# Power.net
KiCad netlist of a schematic drawn in Altium Designer
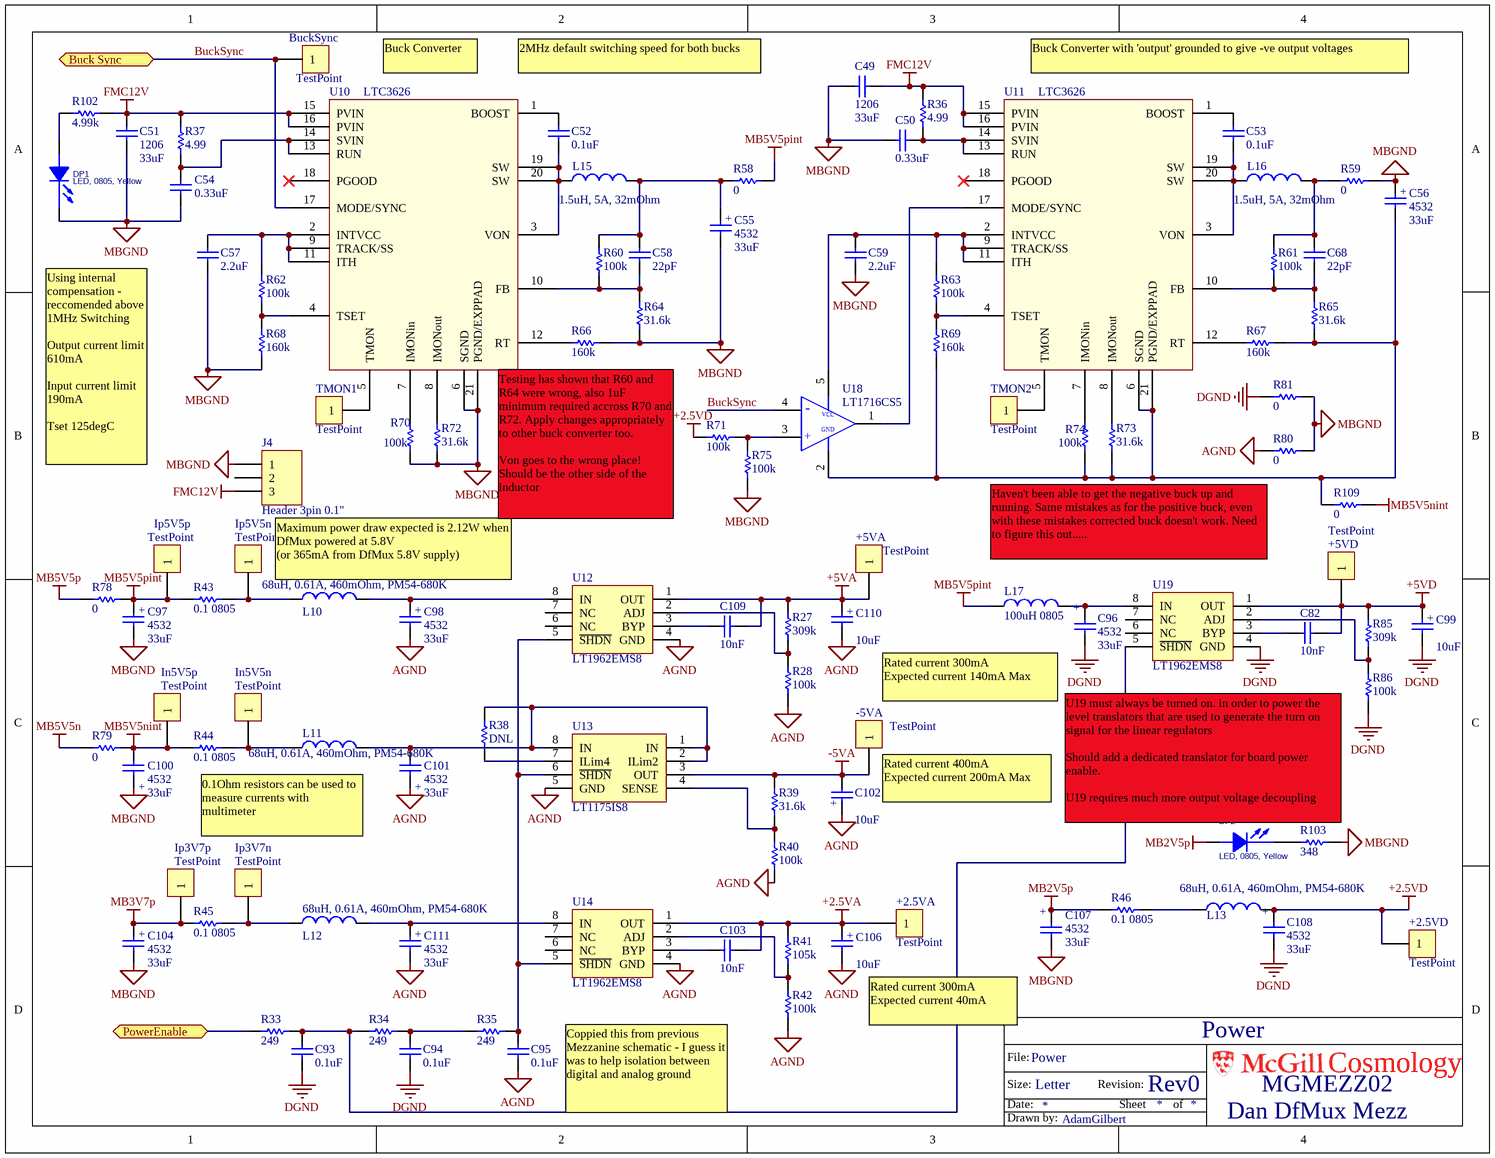
[diagram p0: Power.SchDoc]

(export (version "E")
  (design (tool "Eeschema 10.0.6"))
  (components
    (comp (ref "+2.5VA")
      (value "TestPoint")
      (footprint "TP-3520-SK")
      (description "TestPoint1")
      (libsource (lib "") (part "TestPoint_2"))
    )
    (comp (ref "+2.5VD")
      (value "TestPoint")
      (footprint "TP-3520-SK")
      (description "TestPoint1")
      (libsource (lib "") (part "TestPoint_2"))
    )
    (comp (ref "+5VA")
      (value "TestPoint")
      (footprint "TP-3520-SK")
      (description "TestPoint1")
      (libsource (lib "MGMEZZ04") (part "TestPoint"))
    )
    (comp (ref "+5VD")
      (value "TestPoint")
      (footprint "TP-3520-SK")
      (description "TestPoint1")
      (libsource (lib "MGMEZZ04") (part "TestPoint"))
    )
    (comp (ref "-5VA")
      (value "TestPoint")
      (footprint "TP-3520-SK")
      (description "TestPoint1")
      (libsource (lib "MGMEZZ04") (part "TestPoint"))
    )
    (comp (ref "BuckSync")
      (value "TestPoint")
      (footprint "TP-3520-SK")
      (description "TestPoint1")
      (libsource (lib "") (part "TestPoint_2"))
    )
    (comp (ref "C49")
      (value "33uF")
      (footprint "1206")
      (description "Capacitor, Ceramic, 1210")
      (fields
        (field (name "MANUFACTURER") "TDK Corporation")
        (field (name "MANUFACTURERS PART NUMBER") "C3216X5R1E336M")
      )
      (libsource (lib "MGMEZZ04") (part "CAP 1210"))
    )
    (comp (ref "C50")
      (value "0.33uF")
      (footprint "0603")
      (description "Capacitor, Ceramic, 0603")
      (fields (field (name "MANUFACTURER") "Generic"))
      (libsource (lib "MGMEZZ04") (part "CAP 0603"))
    )
    (comp (ref "C51")
      (value "33uF")
      (footprint "1206")
      (description "Capacitor, Ceramic, 1210")
      (fields
        (field (name "MANUFACTURER") "TDK Corporation")
        (field (name "MANUFACTURERS PART NUMBER") "C3216X5R1E336M")
      )
      (libsource (lib "MGMEZZ04") (part "CAP 1210"))
    )
    (comp (ref "C52")
      (value "0.1uF")
      (footprint "0603")
      (description "Capacitor, Ceramic, 0603")
      (fields (field (name "MANUFACTURER") "Generic"))
      (libsource (lib "MGMEZZ04") (part "CAP 0603"))
    )
    (comp (ref "C53")
      (value "0.1uF")
      (footprint "0603")
      (description "Capacitor, Ceramic, 0603")
      (fields (field (name "MANUFACTURER") "Generic"))
      (libsource (lib "MGMEZZ04") (part "CAP 0603"))
    )
    (comp (ref "C54")
      (value "0.33uF")
      (footprint "0603")
      (description "Capacitor, Ceramic, 0603")
      (fields (field (name "MANUFACTURER") "Generic"))
      (libsource (lib "MGMEZZ04") (part "CAP 0603"))
    )
    (comp (ref "C55")
      (value "33uF")
      (footprint "4532")
      (description "33u, 16V, 20%, 4532C, X5R")
      (fields
        (field (name "MANUFACTURER") "TDK Corporation")
        (field (name "MANUFACTURERS PART NUMBER") "C4532X5R1C336M")
      )
      (libsource (lib "MGMEZZ04") (part "CAP4532"))
    )
    (comp (ref "C56")
      (value "33uF")
      (footprint "4532")
      (description "33u, 16V, 20%, 4532C, X5R")
      (fields
        (field (name "MANUFACTURER") "TDK Corporation")
        (field (name "MANUFACTURERS PART NUMBER") "C4532X5R1C336M")
      )
      (libsource (lib "MGMEZZ04") (part "CAP4532"))
    )
    (comp (ref "C57")
      (value "2.2uF")
      (footprint "0603")
      (description "Capacitor, Ceramic, 0603")
      (fields (field (name "MANUFACTURER") "Generic"))
      (libsource (lib "MGMEZZ04") (part "CAP 0603"))
    )
    (comp (ref "C58")
      (value "22pF")
      (footprint "0603")
      (description "Capacitor, Ceramic, 0603")
      (fields (field (name "MANUFACTURER") "Generic"))
      (libsource (lib "MGMEZZ04") (part "CAP 0603"))
    )
    (comp (ref "C59")
      (value "2.2uF")
      (footprint "0603")
      (description "Capacitor, Ceramic, 0603")
      (fields (field (name "MANUFACTURER") "Generic"))
      (libsource (lib "MGMEZZ04") (part "CAP 0603"))
    )
    (comp (ref "C68")
      (value "22pF")
      (footprint "0603")
      (description "Capacitor, Ceramic, 0603")
      (fields (field (name "MANUFACTURER") "Generic"))
      (libsource (lib "MGMEZZ04") (part "CAP 0603"))
    )
    (comp (ref "C82")
      (value "10nF")
      (footprint "0603")
      (description "Capacitor, Ceramic, 0603")
      (fields (field (name "MANUFACTURER") "Generic"))
      (libsource (lib "MGMEZZ04") (part "CAP 0603"))
    )
    (comp (ref "C93")
      (value "0.1uF")
      (footprint "0603")
      (description "Capacitor, Ceramic, 0603")
      (fields (field (name "MANUFACTURER") "Generic"))
      (libsource (lib "MGMEZZ04") (part "CAP 0603"))
    )
    (comp (ref "C94")
      (value "0.1uF")
      (footprint "0603")
      (description "Capacitor, Ceramic, 0603")
      (fields (field (name "MANUFACTURER") "Generic"))
      (libsource (lib "MGMEZZ04") (part "CAP 0603"))
    )
    (comp (ref "C95")
      (value "0.1uF")
      (footprint "0603")
      (description "Capacitor, Ceramic, 0603")
      (fields (field (name "MANUFACTURER") "Generic"))
      (libsource (lib "MGMEZZ04") (part "CAP 0603"))
    )
    (comp (ref "C96")
      (value "33uF")
      (footprint "4532")
      (description "33u, 16V, 20%, 4532C, X5R")
      (fields
        (field (name "MANUFACTURER") "TDK Corporation")
        (field (name "MANUFACTURERS PART NUMBER") "C4532X5R1C336M")
      )
      (libsource (lib "MGMEZZ04") (part "CAP4532"))
    )
    (comp (ref "C97")
      (value "33uF")
      (footprint "4532")
      (description "33u, 16V, 20%, 4532C, X5R")
      (fields
        (field (name "MANUFACTURER") "TDK Corporation")
        (field (name "MANUFACTURERS PART NUMBER") "C4532X5R1C336M")
      )
      (libsource (lib "MGMEZZ04") (part "CAP4532"))
    )
    (comp (ref "C98")
      (value "33uF")
      (footprint "4532")
      (description "33u, 16V, 20%, 4532C, X5R")
      (fields
        (field (name "MANUFACTURER") "TDK Corporation")
        (field (name "MANUFACTURERS PART NUMBER") "C4532X5R1C336M")
      )
      (libsource (lib "MGMEZZ04") (part "CAP4532"))
    )
    (comp (ref "C99")
      (value "10uF")
      (footprint "TCASE-A")
      (description "TantA Cap")
      (fields (field (name "MANUFACTURER") "Generic"))
      (libsource (lib "MGMEZZ04") (part "CAP TANT CASE-A"))
    )
    (comp (ref "C100")
      (value "33uF")
      (footprint "4532")
      (description "33u, 16V, 20%, 4532C, X5R")
      (fields
        (field (name "MANUFACTURER") "TDK Corporation")
        (field (name "MANUFACTURERS PART NUMBER") "C4532X5R1C336M")
      )
      (libsource (lib "MGMEZZ04") (part "CAP4532"))
    )
    (comp (ref "C101")
      (value "33uF")
      (footprint "4532")
      (description "33u, 16V, 20%, 4532C, X5R")
      (fields
        (field (name "MANUFACTURER") "TDK Corporation")
        (field (name "MANUFACTURERS PART NUMBER") "C4532X5R1C336M")
      )
      (libsource (lib "MGMEZZ04") (part "CAP4532"))
    )
    (comp (ref "C102")
      (value "10uF")
      (footprint "TCASE-A")
      (description "TantA Cap")
      (fields (field (name "MANUFACTURER") "Generic"))
      (libsource (lib "MGMEZZ04") (part "CAP TANT CASE-A"))
    )
    (comp (ref "C103")
      (value "10nF")
      (footprint "0603")
      (description "Capacitor, Ceramic, 0603")
      (fields (field (name "MANUFACTURER") "Generic"))
      (libsource (lib "MGMEZZ04") (part "CAP 0603"))
    )
    (comp (ref "C104")
      (value "33uF")
      (footprint "4532")
      (description "33u, 16V, 20%, 4532C, X5R")
      (fields
        (field (name "MANUFACTURER") "TDK Corporation")
        (field (name "MANUFACTURERS PART NUMBER") "C4532X5R1C336M")
      )
      (libsource (lib "MGMEZZ04") (part "CAP4532"))
    )
    (comp (ref "C106")
      (value "10uF")
      (footprint "TCASE-A")
      (description "TantA Cap")
      (fields (field (name "MANUFACTURER") "Generic"))
      (libsource (lib "MGMEZZ04") (part "CAP TANT CASE-A"))
    )
    (comp (ref "C107")
      (value "33uF")
      (footprint "4532")
      (description "33u, 16V, 20%, 4532C, X5R")
      (fields
        (field (name "MANUFACTURER") "TDK Corporation")
        (field (name "MANUFACTURERS PART NUMBER") "C4532X5R1C336M")
      )
      (libsource (lib "MGMEZZ04") (part "CAP4532"))
    )
    (comp (ref "C108")
      (value "33uF")
      (footprint "4532")
      (description "33u, 16V, 20%, 4532C, X5R")
      (fields
        (field (name "MANUFACTURER") "TDK Corporation")
        (field (name "MANUFACTURERS PART NUMBER") "C4532X5R1C336M")
      )
      (libsource (lib "MGMEZZ04") (part "CAP4532"))
    )
    (comp (ref "C109")
      (value "10nF")
      (footprint "0603")
      (description "Capacitor, Ceramic, 0603")
      (fields (field (name "MANUFACTURER") "Generic"))
      (libsource (lib "MGMEZZ04") (part "CAP 0603"))
    )
    (comp (ref "C110")
      (value "10uF")
      (footprint "TCASE-A")
      (description "TantA Cap")
      (fields (field (name "MANUFACTURER") "Generic"))
      (libsource (lib "MGMEZZ04") (part "CAP TANT CASE-A"))
    )
    (comp (ref "C111")
      (value "33uF")
      (footprint "4532")
      (description "33u, 16V, 20%, 4532C, X5R")
      (fields
        (field (name "MANUFACTURER") "TDK Corporation")
        (field (name "MANUFACTURERS PART NUMBER") "C4532X5R1C336M")
      )
      (libsource (lib "MGMEZZ04") (part "CAP4532"))
    )
    (comp (ref "DP1")
      (value "LED, 0805, Yellow")
      (description "LED")
      (fields
        (field (name "MANUFACTURER") "Rohm Semiconductor")
        (field (name "MANUFACTURERS PART NUMBER") "SML-211YTT86")
      )
      (libsource (lib "MGMEZZ04") (part "LED, yellow, 0805, 2mA"))
    )
    (comp (ref "DP2")
      (value "LED, 0805, Yellow")
      (description "LED")
      (fields
        (field (name "MANUFACTURER") "Rohm Semiconductor")
        (field (name "MANUFACTURERS PART NUMBER") "SML-211YTT86")
      )
      (libsource (lib "MGMEZZ04") (part "LED, yellow, 0805, 2mA"))
    )
    (comp (ref "In5V5n")
      (value "TestPoint")
      (footprint "TP-3520-SK")
      (description "TestPoint1")
      (libsource (lib "MGMEZZ04") (part "TestPoint"))
    )
    (comp (ref "In5V5p")
      (value "TestPoint")
      (footprint "TP-3520-SK")
      (description "TestPoint1")
      (libsource (lib "MGMEZZ04") (part "TestPoint"))
    )
    (comp (ref "Ip3V7n")
      (value "TestPoint")
      (footprint "TP-3520-SK")
      (description "TestPoint1")
      (libsource (lib "MGMEZZ04") (part "TestPoint"))
    )
    (comp (ref "Ip3V7p")
      (value "TestPoint")
      (footprint "TP-3520-SK")
      (description "TestPoint1")
      (libsource (lib "MGMEZZ04") (part "TestPoint"))
    )
    (comp (ref "Ip5V5n")
      (value "TestPoint")
      (footprint "TP-3520-SK")
      (description "TestPoint1")
      (libsource (lib "MGMEZZ04") (part "TestPoint"))
    )
    (comp (ref "Ip5V5p")
      (value "TestPoint")
      (footprint "TP-3520-SK")
      (description "TestPoint1")
      (libsource (lib "MGMEZZ04") (part "TestPoint"))
    )
    (comp (ref "J4")
      (value "Header 3pin 0.1\"")
      (footprint "HDR1X3_MolexVertical")
      (description "Header, 0.1\"  3-Pin")
      (fields (field (name "MANUFACTURER") "Molex") (field (name "MANUFACTURERS PART NUMBER") "0099990987"))
      (libsource (lib "MGMEZZ04") (part "Header 3"))
    )
    (comp (ref "L10")
      (value "68uH")
      (footprint "CHOKEPM54")
      (description "Inductor PM54")
      (fields
        (field (name "MANUFACTURER") "Bourns Inc.")
        (field (name "MANUFACTURERS PART NUMBER") "PM54-680K")
        (field (name "PART CONSTRAINTS") "68uH, 0.61A, 460mOhm, PM54-680K")
      )
      (libsource (lib "") (part "INDPM54_1"))
    )
    (comp (ref "L11")
      (value "68uH")
      (footprint "CHOKEPM54")
      (description "Inductor PM54")
      (fields
        (field (name "MANUFACTURER") "Bourns Inc.")
        (field (name "MANUFACTURERS PART NUMBER") "PM54-680K")
        (field (name "PART CONSTRAINTS") "68uH, 0.61A, 460mOhm, PM54-680K")
      )
      (libsource (lib "MGMEZZ04") (part "INDPM54"))
    )
    (comp (ref "L12")
      (value "68uH")
      (footprint "CHOKEPM54")
      (description "Inductor PM54")
      (fields
        (field (name "MANUFACTURER") "Bourns Inc.")
        (field (name "MANUFACTURERS PART NUMBER") "PM54-680K")
        (field (name "PART CONSTRAINTS") "68uH, 0.61A, 460mOhm, PM54-680K")
      )
      (libsource (lib "") (part "INDPM54_1"))
    )
    (comp (ref "L13")
      (value "68uH")
      (footprint "CHOKEPM54")
      (description "Inductor PM54")
      (fields
        (field (name "MANUFACTURER") "Bourns Inc.")
        (field (name "MANUFACTURERS PART NUMBER") "PM54-680K")
        (field (name "PART CONSTRAINTS") "68uH, 0.61A, 460mOhm, PM54-680K")
      )
      (libsource (lib "MGMEZZ04") (part "INDPM54"))
    )
    (comp (ref "L15")
      (value "1.5uH")
      (footprint "IHLP-1212")
      (description "Inductor IHLP1212")
      (fields
        (field (name "MANUFACTURER") "Vishay Dale")
        (field (name "MANUFACTURERS PART NUMBER") "IHLP1212BZER1R5M11")
        (field (name "PART CONSTRAINTS") "1.5uH, 5A, 32mOhm")
      )
      (libsource (lib "MGMEZZ04") (part "IND IHLP1212"))
    )
    (comp (ref "L16")
      (value "1.5uH")
      (footprint "IHLP-1212")
      (description "Inductor IHLP1212")
      (fields
        (field (name "MANUFACTURER") "Vishay Dale")
        (field (name "MANUFACTURERS PART NUMBER") "IHLP1212BZER1R5M11")
        (field (name "PART CONSTRAINTS") "1.5uH, 5A, 32mOhm")
      )
      (libsource (lib "MGMEZZ04") (part "IND IHLP1212"))
    )
    (comp (ref "L17")
      (value "100uH 0805")
      (footprint "0805")
      (description "Inductor 0805")
      (fields
        (field (name "MANUFACTURER") "TDK Corporation")
        (field (name "MANUFACTURERS PART NUMBER") "GLCR2012T101M-HC")
      )
      (libsource (lib "MGMEZZ04") (part "IND 0805"))
    )
    (comp (ref "R27")
      (value "309k")
      (footprint "0603")
      (description "Resistor")
      (fields (field (name "MANUFACTURER") "Generic"))
      (libsource (lib "MGMEZZ04") (part "RES 0603"))
    )
    (comp (ref "R28")
      (value "100k")
      (footprint "0603")
      (description "Resistor")
      (fields (field (name "MANUFACTURER") "Generic"))
      (libsource (lib "MGMEZZ04") (part "RES 0603"))
    )
    (comp (ref "R33")
      (value "249")
      (footprint "0603")
      (description "Resistor")
      (fields (field (name "MANUFACTURER") "Generic"))
      (libsource (lib "MGMEZZ04") (part "RES 0603"))
    )
    (comp (ref "R34")
      (value "249")
      (footprint "0603")
      (description "Resistor")
      (fields (field (name "MANUFACTURER") "Generic"))
      (libsource (lib "MGMEZZ04") (part "RES 0603"))
    )
    (comp (ref "R35")
      (value "249")
      (footprint "0603")
      (description "Resistor")
      (fields (field (name "MANUFACTURER") "Generic"))
      (libsource (lib "MGMEZZ04") (part "RES 0603"))
    )
    (comp (ref "R36")
      (value "4.99")
      (footprint "0603")
      (description "Resistor")
      (fields (field (name "MANUFACTURER") "Generic"))
      (libsource (lib "MGMEZZ04") (part "RES 0603"))
    )
    (comp (ref "R37")
      (value "4.99")
      (footprint "0603")
      (description "Resistor")
      (fields (field (name "MANUFACTURER") "Generic"))
      (libsource (lib "MGMEZZ04") (part "RES 0603"))
    )
    (comp (ref "R38")
      (value "DNL")
      (footprint "0603")
      (description "Resistor")
      (fields (field (name "MANUFACTURER") "Generic"))
      (libsource (lib "MGMEZZ04") (part "RES 0603"))
    )
    (comp (ref "R39")
      (value "31.6k")
      (footprint "0603")
      (description "Resistor")
      (fields (field (name "MANUFACTURER") "Generic"))
      (libsource (lib "MGMEZZ04") (part "RES 0603"))
    )
    (comp (ref "R40")
      (value "100k")
      (footprint "0603")
      (description "Resistor")
      (fields (field (name "MANUFACTURER") "Generic"))
      (libsource (lib "MGMEZZ04") (part "RES 0603"))
    )
    (comp (ref "R41")
      (value "105k")
      (footprint "0603")
      (description "Resistor")
      (fields (field (name "MANUFACTURER") "Generic"))
      (libsource (lib "MGMEZZ04") (part "RES 0603"))
    )
    (comp (ref "R42")
      (value "100k")
      (footprint "0603")
      (description "Resistor")
      (fields (field (name "MANUFACTURER") "Generic"))
      (libsource (lib "MGMEZZ04") (part "RES 0603"))
    )
    (comp (ref "R43")
      (value "0.1 0805")
      (footprint "0805")
      (description "RES 0.1 OHM 1/8W 0805 SMD")
      (fields
        (field (name "MANUFACTURER") "Panasonic Electronic Components")
        (field (name "MANUFACTURERS PART NUMBER") "ERJ-L06KF10CV")
      )
      (libsource (lib "MGMEZZ04") (part "RES 0805"))
    )
    (comp (ref "R44")
      (value "0.1 0805")
      (footprint "0805")
      (description "RES 0.1 OHM 1/8W 0805 SMD")
      (fields
        (field (name "MANUFACTURER") "Panasonic Electronic Components")
        (field (name "MANUFACTURERS PART NUMBER") "ERJ-L06KF10CV")
      )
      (libsource (lib "MGMEZZ04") (part "RES 0805"))
    )
    (comp (ref "R45")
      (value "0.1 0805")
      (footprint "0805")
      (description "RES 0.1 OHM 1/8W 0805 SMD")
      (fields
        (field (name "MANUFACTURER") "Panasonic Electronic Components")
        (field (name "MANUFACTURERS PART NUMBER") "ERJ-L06KF10CV")
      )
      (libsource (lib "MGMEZZ04") (part "RES 0805"))
    )
    (comp (ref "R46")
      (value "0.1 0805")
      (footprint "0805")
      (description "RES 0.1 OHM 1/8W 0805 SMD")
      (fields
        (field (name "MANUFACTURER") "Panasonic Electronic Components")
        (field (name "MANUFACTURERS PART NUMBER") "ERJ-L06KF10CV")
      )
      (libsource (lib "MGMEZZ04") (part "RES 0805"))
    )
    (comp (ref "R58")
      (value "0")
      (footprint "0805")
      (description "RES 0.0 OHM 1/8W 0805 SMD")
      (fields (field (name "MANUFACTURER") "Generic"))
      (libsource (lib "MGMEZZ04") (part "RES 0805"))
    )
    (comp (ref "R59")
      (value "0")
      (footprint "0805")
      (description "RES 0.0 OHM 1/8W 0805 SMD")
      (fields (field (name "MANUFACTURER") "Generic"))
      (libsource (lib "MGMEZZ04") (part "RES 0805"))
    )
    (comp (ref "R60")
      (value "100k")
      (footprint "0603")
      (description "Resistor")
      (fields (field (name "MANUFACTURER") "Generic"))
      (libsource (lib "MGMEZZ04") (part "RES 0603"))
    )
    (comp (ref "R61")
      (value "100k")
      (footprint "0603")
      (description "Resistor")
      (fields (field (name "MANUFACTURER") "Generic"))
      (libsource (lib "MGMEZZ04") (part "RES 0603"))
    )
    (comp (ref "R62")
      (value "100k")
      (footprint "0603")
      (description "Resistor")
      (fields (field (name "MANUFACTURER") "Generic"))
      (libsource (lib "MGMEZZ04") (part "RES 0603"))
    )
    (comp (ref "R63")
      (value "100k")
      (footprint "0603")
      (description "Resistor")
      (fields (field (name "MANUFACTURER") "Generic"))
      (libsource (lib "MGMEZZ04") (part "RES 0603"))
    )
    (comp (ref "R64")
      (value "31.6k")
      (footprint "0603")
      (description "Resistor")
      (fields (field (name "MANUFACTURER") "Generic"))
      (libsource (lib "MGMEZZ04") (part "RES 0603"))
    )
    (comp (ref "R65")
      (value "31.6k")
      (footprint "0603")
      (description "Resistor")
      (fields (field (name "MANUFACTURER") "Generic"))
      (libsource (lib "MGMEZZ04") (part "RES 0603"))
    )
    (comp (ref "R66")
      (value "160k")
      (footprint "0603")
      (description "Resistor")
      (fields (field (name "MANUFACTURER") "Generic"))
      (libsource (lib "MGMEZZ04") (part "RES 0603"))
    )
    (comp (ref "R67")
      (value "160k")
      (footprint "0603")
      (description "Resistor")
      (fields (field (name "MANUFACTURER") "Generic"))
      (libsource (lib "MGMEZZ04") (part "RES 0603"))
    )
    (comp (ref "R68")
      (value "160k")
      (footprint "0603")
      (description "Resistor")
      (fields (field (name "MANUFACTURER") "Generic"))
      (libsource (lib "MGMEZZ04") (part "RES 0603"))
    )
    (comp (ref "R69")
      (value "160k")
      (footprint "0603")
      (description "Resistor")
      (fields (field (name "MANUFACTURER") "Generic"))
      (libsource (lib "MGMEZZ04") (part "RES 0603"))
    )
    (comp (ref "R70")
      (value "100k")
      (footprint "0603")
      (description "Resistor")
      (fields (field (name "MANUFACTURER") "Generic"))
      (libsource (lib "MGMEZZ04") (part "RES 0603"))
    )
    (comp (ref "R71")
      (value "100k")
      (footprint "0603")
      (description "Resistor")
      (fields (field (name "MANUFACTURER") "Generic"))
      (libsource (lib "MGMEZZ04") (part "RES 0603"))
    )
    (comp (ref "R72")
      (value "31.6k")
      (footprint "0603")
      (description "Resistor")
      (fields (field (name "MANUFACTURER") "Generic"))
      (libsource (lib "MGMEZZ04") (part "RES 0603"))
    )
    (comp (ref "R73")
      (value "31.6k")
      (footprint "0603")
      (description "Resistor")
      (fields (field (name "MANUFACTURER") "Generic"))
      (libsource (lib "MGMEZZ04") (part "RES 0603"))
    )
    (comp (ref "R74")
      (value "100k")
      (footprint "0603")
      (description "Resistor")
      (fields (field (name "MANUFACTURER") "Generic"))
      (libsource (lib "MGMEZZ04") (part "RES 0603"))
    )
    (comp (ref "R75")
      (value "100k")
      (footprint "0603")
      (description "Resistor")
      (fields (field (name "MANUFACTURER") "Generic"))
      (libsource (lib "MGMEZZ04") (part "RES 0603"))
    )
    (comp (ref "R78")
      (value "0")
      (footprint "0805")
      (description "RES 0.0 OHM 1/8W 0805 SMD")
      (fields (field (name "MANUFACTURER") "Generic"))
      (libsource (lib "MGMEZZ04") (part "RES 0805"))
    )
    (comp (ref "R79")
      (value "0")
      (footprint "0805")
      (description "RES 0.0 OHM 1/8W 0805 SMD")
      (fields (field (name "MANUFACTURER") "Generic"))
      (libsource (lib "MGMEZZ04") (part "RES 0805"))
    )
    (comp (ref "R80")
      (value "0")
      (footprint "1206")
      (description "RES 0.0 OHM 1/8W 1206 SMD")
      (fields (field (name "MANUFACTURER") "Generic"))
      (libsource (lib "MGMEZZ04") (part "RES 1206"))
    )
    (comp (ref "R81")
      (value "0")
      (footprint "1206")
      (description "RES 0.0 OHM 1/8W 1206 SMD")
      (fields (field (name "MANUFACTURER") "Generic"))
      (libsource (lib "MGMEZZ04") (part "RES 1206"))
    )
    (comp (ref "R85")
      (value "309k")
      (footprint "0603")
      (description "Resistor")
      (fields (field (name "MANUFACTURER") "Generic"))
      (libsource (lib "MGMEZZ04") (part "RES 0603"))
    )
    (comp (ref "R86")
      (value "100k")
      (footprint "0603")
      (description "Resistor")
      (fields (field (name "MANUFACTURER") "Generic"))
      (libsource (lib "MGMEZZ04") (part "RES 0603"))
    )
    (comp (ref "R102")
      (value "4.99k")
      (footprint "0603")
      (description "Resistor")
      (fields (field (name "MANUFACTURER") "Generic"))
      (libsource (lib "MGMEZZ04") (part "RES 0603"))
    )
    (comp (ref "R103")
      (value "348")
      (footprint "0603")
      (description "Resistor")
      (fields (field (name "MANUFACTURER") "Generic"))
      (libsource (lib "MGMEZZ04") (part "RES 0603"))
    )
    (comp (ref "R109")
      (value "0")
      (footprint "0805")
      (description "RES 0.0 OHM 1/8W 0805 SMD")
      (fields (field (name "MANUFACTURER") "Generic"))
      (libsource (lib "MGMEZZ04") (part "RES 0805"))
    )
    (comp (ref "TMON1")
      (value "TestPoint")
      (footprint "TP-3520-SK")
      (description "TestPoint1")
      (libsource (lib "") (part "TestPoint_1"))
    )
    (comp (ref "TMON2")
      (value "TestPoint")
      (footprint "TP-3520-SK")
      (description "TestPoint1")
      (libsource (lib "") (part "TestPoint_1"))
    )
    (comp (ref "U10")
      (value "LTC3626")
      (footprint "LTC3626")
      (description "20V, 2.5A Sync buck, 3Mhz")
      (fields
        (field (name "MANUFACTURERS PART NUMBER") "LTC3626EUDC#PBF")
        (field (name "MANUFACTURER") "Linear Technology")
      )
      (libsource (lib "MGMEZZ04") (part "LTC3626"))
    )
    (comp (ref "U11")
      (value "LTC3626")
      (footprint "LTC3626")
      (description "20V, 2.5A Sync buck, 3Mhz")
      (fields
        (field (name "MANUFACTURERS PART NUMBER") "LTC3626EUDC#PBF")
        (field (name "MANUFACTURER") "Linear Technology")
      )
      (libsource (lib "MGMEZZ04") (part "LTC3626"))
    )
    (comp (ref "U12")
      (value "LT1962EMS8")
      (footprint "MSOP-8")
      (description "REG, micropower, low noise, low  dropout")
      (fields
        (field (name "MANUFACTURER") "Linear Technology")
        (field (name "MANUFACTURERS PART NUMBER") "LT1962EMS8#PBF")
      )
      (libsource (lib "MGMEZZ04") (part "LT1962EMS8"))
    )
    (comp (ref "U13")
      (value "LT1175IS8")
      (footprint "SO8")
      (description "REG, negative micropower low dropout")
      (fields
        (field (name "MANUFACTURER") "Linear Technology")
        (field (name "MANUFACTURERS PART NUMBER") "LT1175IS8#PBF")
      )
      (libsource (lib "MGMEZZ04") (part "LT1175IS8"))
    )
    (comp (ref "U14")
      (value "LT1962EMS8")
      (footprint "MSOP-8")
      (description "REG, micropower, low noise, low  dropout")
      (fields
        (field (name "MANUFACTURER") "Linear Technology")
        (field (name "MANUFACTURERS PART NUMBER") "LT1962EMS8#PBF")
      )
      (libsource (lib "MGMEZZ04") (part "LT1962EMS8"))
    )
    (comp (ref "U18")
      (value "LT1716CS5")
      (footprint "SOT23-5")
      (description "Comparator 2.7V to 44V rail to rail")
      (fields
        (field (name "MANUFACTURER") "Linear Technology")
        (field (name "MANUFACTURERS PART NUMBER") "LT1716CS5#TRMPBF")
      )
      (libsource (lib "MGMEZZ04") (part "LT1716CS5"))
    )
    (comp (ref "U19")
      (value "LT1962EMS8")
      (footprint "MSOP-8")
      (description "REG, micropower, low noise, low  dropout")
      (fields
        (field (name "MANUFACTURER") "Linear Technology")
        (field (name "MANUFACTURERS PART NUMBER") "LT1962EMS8#PBF")
      )
      (libsource (lib "MGMEZZ04") (part "LT1962EMS8"))
    )
  )
  (nets
    (net (code "1") (name "+2.5VA") (class "Default")
      (node (ref "+2.5VA") (pin "1") (pinfunction "1_1") (pintype "passive"))
      (node (ref "C103") (pin "2") (pinfunction "2_2") (pintype "passive"))
      (node (ref "C106") (pin "1") (pinfunction "1_1") (pintype "passive"))
      (node (ref "R41") (pin "1") (pinfunction "1_1") (pintype "passive"))
      (node (ref "U14") (pin "1") (pinfunction "OUT_1") (pintype "power_in"))
    )
    (net (code "2") (name "+2.5VD") (class "Default")
      (node (ref "+2.5VD") (pin "1") (pinfunction "1_1") (pintype "passive"))
      (node (ref "C108") (pin "1") (pinfunction "1_1") (pintype "passive"))
      (node (ref "L13") (pin "1") (pinfunction "1_1") (pintype "passive"))
      (node (ref "R71") (pin "2") (pinfunction "2_2") (pintype "passive"))
    )
    (net (code "3") (name "+5VA") (class "Default")
      (node (ref "+5VA") (pin "1") (pinfunction "1_1") (pintype "passive"))
      (node (ref "C109") (pin "2") (pinfunction "2_2") (pintype "passive"))
      (node (ref "C110") (pin "1") (pinfunction "1_1") (pintype "passive"))
      (node (ref "R27") (pin "1") (pinfunction "1_1") (pintype "passive"))
      (node (ref "U12") (pin "1") (pinfunction "OUT_1") (pintype "power_in"))
    )
    (net (code "4") (name "+5VD") (class "Default")
      (node (ref "+5VD") (pin "1") (pinfunction "1_1") (pintype "passive"))
      (node (ref "C82") (pin "2") (pinfunction "2_2") (pintype "passive"))
      (node (ref "C99") (pin "1") (pinfunction "1_1") (pintype "passive"))
      (node (ref "R85") (pin "1") (pinfunction "1_1") (pintype "passive"))
      (node (ref "U19") (pin "1") (pinfunction "OUT_1") (pintype "power_in"))
    )
    (net (code "5") (name "-5VA") (class "Default")
      (node (ref "-5VA") (pin "1") (pinfunction "1_1") (pintype "passive"))
      (node (ref "C102") (pin "2") (pinfunction "2_2") (pintype "passive"))
      (node (ref "R39") (pin "1") (pinfunction "1_1") (pintype "passive"))
      (node (ref "U13") (pin "3") (pinfunction "OUT_3") (pintype "passive"))
    )
    (net (code "6") (name "/BuckSync") (class "Default")
      (node (ref "BuckSync") (pin "1") (pinfunction "1_1") (pintype "passive"))
      (node (ref "U10") (pin "17") (pinfunction "MODE/SYNC_17") (pintype "passive"))
      (node (ref "U18") (pin "4") (pinfunction "-_4") (pintype "power_in"))
    )
    (net (code "7") (name "/PowerEnable") (class "Default")
      (node (ref "R33") (pin "1") (pinfunction "1_1") (pintype "passive"))
    )
    (net (code "8") (name "AGND") (class "Default")
      (node (ref "C101") (pin "1") (pinfunction "1_1") (pintype "passive"))
      (node (ref "C102") (pin "1") (pinfunction "1_1") (pintype "passive"))
      (node (ref "C106") (pin "2") (pinfunction "2_2") (pintype "passive"))
      (node (ref "C110") (pin "2") (pinfunction "2_2") (pintype "passive"))
      (node (ref "C111") (pin "2") (pinfunction "2_2") (pintype "passive"))
      (node (ref "C95") (pin "2") (pinfunction "2_2") (pintype "passive"))
      (node (ref "C98") (pin "2") (pinfunction "2_2") (pintype "passive"))
      (node (ref "R28") (pin "2") (pinfunction "2_2") (pintype "passive"))
      (node (ref "R40") (pin "2") (pinfunction "2_2") (pintype "passive"))
      (node (ref "R42") (pin "2") (pinfunction "2_2") (pintype "passive"))
      (node (ref "R80") (pin "2") (pinfunction "2_2") (pintype "passive"))
      (node (ref "U12") (pin "4") (pinfunction "GND_4") (pintype "power_in"))
      (node (ref "U13") (pin "5") (pinfunction "GND_5") (pintype "passive"))
      (node (ref "U14") (pin "4") (pinfunction "GND_4") (pintype "power_in"))
    )
    (net (code "9") (name "DGND") (class "Default")
      (node (ref "C108") (pin "2") (pinfunction "2_2") (pintype "passive"))
      (node (ref "C93") (pin "1") (pinfunction "1_1") (pintype "passive"))
      (node (ref "C94") (pin "2") (pinfunction "2_2") (pintype "passive"))
      (node (ref "C96") (pin "2") (pinfunction "2_2") (pintype "passive"))
      (node (ref "C99") (pin "2") (pinfunction "2_2") (pintype "passive"))
      (node (ref "R81") (pin "2") (pinfunction "2_2") (pintype "passive"))
      (node (ref "R86") (pin "2") (pinfunction "2_2") (pintype "passive"))
      (node (ref "U19") (pin "4") (pinfunction "GND_4") (pintype "power_in"))
    )
    (net (code "10") (name "FMC12V") (class "Default")
      (node (ref "C49") (pin "1") (pinfunction "1_1") (pintype "passive"))
      (node (ref "C51") (pin "1") (pinfunction "1_1") (pintype "passive"))
      (node (ref "J4") (pin "3") (pinfunction "3_3") (pintype "passive"))
      (node (ref "R102") (pin "2") (pinfunction "2_2") (pintype "passive"))
      (node (ref "R36") (pin "2") (pinfunction "2_2") (pintype "passive"))
      (node (ref "R37") (pin "1") (pinfunction "1_1") (pintype "passive"))
      (node (ref "U10") (pin "15") (pinfunction "PVIN_15") (pintype "passive"))
      (node (ref "U10") (pin "16") (pinfunction "PVIN_16") (pintype "passive"))
      (node (ref "U11") (pin "15") (pinfunction "PVIN_15") (pintype "passive"))
      (node (ref "U11") (pin "16") (pinfunction "PVIN_16") (pintype "passive"))
    )
    (net (code "11") (name "MB2V5p") (class "Default")
      (node (ref "C107") (pin "1") (pinfunction "1_1") (pintype "passive"))
      (node (ref "DP2") (pin "1") (pinfunction "ANODE_1") (pintype "passive"))
      (node (ref "R46") (pin "1") (pinfunction "1_1") (pintype "passive"))
    )
    (net (code "12") (name "MB3V7p") (class "Default")
      (node (ref "C104") (pin "1") (pinfunction "1_1") (pintype "passive"))
      (node (ref "Ip3V7p") (pin "1") (pinfunction "1_1") (pintype "passive"))
      (node (ref "R45") (pin "1") (pinfunction "1_1") (pintype "passive"))
    )
    (net (code "13") (name "MB5V5n") (class "Default")
      (node (ref "R79") (pin "1") (pinfunction "1_1") (pintype "passive"))
    )
    (net (code "14") (name "MB5V5nint") (class "Default")
      (node (ref "C100") (pin "2") (pinfunction "2_2") (pintype "passive"))
      (node (ref "In5V5p") (pin "1") (pinfunction "1_1") (pintype "passive"))
      (node (ref "R109") (pin "1") (pinfunction "1_1") (pintype "passive"))
      (node (ref "R44") (pin "1") (pinfunction "1_1") (pintype "passive"))
      (node (ref "R79") (pin "2") (pinfunction "2_2") (pintype "passive"))
    )
    (net (code "15") (name "MB5V5p") (class "Default")
      (node (ref "R78") (pin "1") (pinfunction "1_1") (pintype "passive"))
    )
    (net (code "16") (name "MB5V5pint") (class "Default")
      (node (ref "C97") (pin "1") (pinfunction "1_1") (pintype "passive"))
      (node (ref "Ip5V5p") (pin "1") (pinfunction "1_1") (pintype "passive"))
      (node (ref "L17") (pin "1") (pinfunction "1_1") (pintype "passive"))
      (node (ref "R43") (pin "1") (pinfunction "1_1") (pintype "passive"))
      (node (ref "R58") (pin "2") (pinfunction "2_2") (pintype "passive"))
      (node (ref "R78") (pin "2") (pinfunction "2_2") (pintype "passive"))
    )
    (net (code "17") (name "MBGND") (class "Default")
      (node (ref "C100") (pin "1") (pinfunction "1_1") (pintype "passive"))
      (node (ref "C104") (pin "2") (pinfunction "2_2") (pintype "passive"))
      (node (ref "C107") (pin "2") (pinfunction "2_2") (pintype "passive"))
      (node (ref "C49") (pin "2") (pinfunction "2_2") (pintype "passive"))
      (node (ref "C50") (pin "1") (pinfunction "1_1") (pintype "passive"))
      (node (ref "C51") (pin "2") (pinfunction "2_2") (pintype "passive"))
      (node (ref "C54") (pin "1") (pinfunction "1_1") (pintype "passive"))
      (node (ref "C55") (pin "2") (pinfunction "2_2") (pintype "passive"))
      (node (ref "C56") (pin "1") (pinfunction "1_1") (pintype "passive"))
      (node (ref "C57") (pin "1") (pinfunction "1_1") (pintype "passive"))
      (node (ref "C59") (pin "1") (pinfunction "1_1") (pintype "passive"))
      (node (ref "C97") (pin "2") (pinfunction "2_2") (pintype "passive"))
      (node (ref "DP1") (pin "2") (pinfunction "CATHODE_2") (pintype "passive"))
      (node (ref "J4") (pin "1") (pinfunction "1_1") (pintype "passive"))
      (node (ref "R103") (pin "1") (pinfunction "1_1") (pintype "passive"))
      (node (ref "R59") (pin "2") (pinfunction "2_2") (pintype "passive"))
      (node (ref "R64") (pin "1") (pinfunction "1_1") (pintype "passive"))
      (node (ref "R66") (pin "1") (pinfunction "1_1") (pintype "passive"))
      (node (ref "R68") (pin "2") (pinfunction "2_2") (pintype "passive"))
      (node (ref "R70") (pin "1") (pinfunction "1_1") (pintype "passive"))
      (node (ref "R72") (pin "1") (pinfunction "1_1") (pintype "passive"))
      (node (ref "R75") (pin "2") (pinfunction "2_2") (pintype "passive"))
      (node (ref "R80") (pin "1") (pinfunction "1_1") (pintype "passive"))
      (node (ref "R81") (pin "1") (pinfunction "1_1") (pintype "passive"))
      (node (ref "U10") (pin "21") (pinfunction "PGND/EXPPAD_21") (pintype "passive"))
      (node (ref "U10") (pin "6") (pinfunction "SGND_6") (pintype "passive"))
    )
    (net (code "18") (name "Net-(C55-Pad1)") (class "Default")
      (node (ref "C55") (pin "1") (pinfunction "1_1") (pintype "passive"))
      (node (ref "C58") (pin "2") (pinfunction "2_2") (pintype "passive"))
      (node (ref "L15") (pin "2") (pinfunction "2_2") (pintype "passive"))
      (node (ref "R58") (pin "1") (pinfunction "1_1") (pintype "passive"))
      (node (ref "R60") (pin "2") (pinfunction "2_2") (pintype "passive"))
    )
    (net (code "19") (name "Net-(C68-Pad2)") (class "Default")
      (node (ref "C68") (pin "2") (pinfunction "2_2") (pintype "passive"))
      (node (ref "L16") (pin "2") (pinfunction "2_2") (pintype "passive"))
      (node (ref "R59") (pin "1") (pinfunction "1_1") (pintype "passive"))
      (node (ref "R61") (pin "2") (pinfunction "2_2") (pintype "passive"))
    )
    (net (code "20") (name "Net-(C94-Pad1)") (class "Default")
      (node (ref "C94") (pin "1") (pinfunction "1_1") (pintype "passive"))
      (node (ref "R34") (pin "2") (pinfunction "2_2") (pintype "passive"))
      (node (ref "R35") (pin "1") (pinfunction "1_1") (pintype "passive"))
    )
    (net (code "21") (name "Net-(DP1-ANODE)") (class "Default")
      (node (ref "DP1") (pin "1") (pinfunction "ANODE_1") (pintype "passive"))
      (node (ref "R102") (pin "1") (pinfunction "1_1") (pintype "passive"))
    )
    (net (code "22") (name "Net-(DP2-CATHODE)") (class "Default")
      (node (ref "DP2") (pin "2") (pinfunction "CATHODE_2") (pintype "passive"))
      (node (ref "R103") (pin "2") (pinfunction "2_2") (pintype "passive"))
    )
    (net (code "23") (name "Net-(In5V5n-Pad1)") (class "Default")
      (node (ref "In5V5n") (pin "1") (pinfunction "1_1") (pintype "passive"))
      (node (ref "L11") (pin "2") (pinfunction "2_2") (pintype "passive"))
      (node (ref "R44") (pin "2") (pinfunction "2_2") (pintype "passive"))
    )
    (net (code "24") (name "Net-(Ip3V7n-Pad1)") (class "Default")
      (node (ref "Ip3V7n") (pin "1") (pinfunction "1_1") (pintype "passive"))
      (node (ref "L12") (pin "1") (pinfunction "1_1") (pintype "passive"))
      (node (ref "R45") (pin "2") (pinfunction "2_2") (pintype "passive"))
    )
    (net (code "25") (name "Net-(Ip5V5n-Pad1)") (class "Default")
      (node (ref "Ip5V5n") (pin "1") (pinfunction "1_1") (pintype "passive"))
      (node (ref "L10") (pin "1") (pinfunction "1_1") (pintype "passive"))
      (node (ref "R43") (pin "2") (pinfunction "2_2") (pintype "passive"))
    )
    (net (code "26") (name "Net-(L13-Pad2)") (class "Default")
      (node (ref "L13") (pin "2") (pinfunction "2_2") (pintype "passive"))
      (node (ref "R46") (pin "2") (pinfunction "2_2") (pintype "passive"))
    )
    (net (code "27") (name "Net-(U10-BOOST)") (class "Default")
      (node (ref "C52") (pin "2") (pinfunction "2_2") (pintype "passive"))
      (node (ref "U10") (pin "1") (pinfunction "BOOST_1") (pintype "passive"))
    )
    (net (code "28") (name "Net-(U10-FB)") (class "Default")
      (node (ref "C58") (pin "1") (pinfunction "1_1") (pintype "passive"))
      (node (ref "R60") (pin "1") (pinfunction "1_1") (pintype "passive"))
      (node (ref "R64") (pin "2") (pinfunction "2_2") (pintype "passive"))
      (node (ref "U10") (pin "10") (pinfunction "FB_10") (pintype "passive"))
    )
    (net (code "29") (name "Net-(U10-IMONin)") (class "Default")
      (node (ref "R70") (pin "2") (pinfunction "2_2") (pintype "passive"))
      (node (ref "U10") (pin "7") (pinfunction "IMONin_7") (pintype "passive"))
    )
    (net (code "30") (name "Net-(U10-IMONout)") (class "Default")
      (node (ref "R72") (pin "2") (pinfunction "2_2") (pintype "passive"))
      (node (ref "U10") (pin "8") (pinfunction "IMONout_8") (pintype "passive"))
    )
    (net (code "31") (name "Net-(U10-INTVCC)") (class "Default")
      (node (ref "C57") (pin "2") (pinfunction "2_2") (pintype "passive"))
      (node (ref "R62") (pin "2") (pinfunction "2_2") (pintype "passive"))
      (node (ref "U10") (pin "11") (pinfunction "ITH_11") (pintype "passive"))
      (node (ref "U10") (pin "2") (pinfunction "INTVCC_2") (pintype "passive"))
      (node (ref "U10") (pin "9") (pinfunction "TRACK/SS_9") (pintype "passive"))
    )
    (net (code "32") (name "Net-(U10-RT)") (class "Default")
      (node (ref "R66") (pin "2") (pinfunction "2_2") (pintype "passive"))
      (node (ref "U10") (pin "12") (pinfunction "RT_12") (pintype "passive"))
    )
    (net (code "33") (name "Net-(U10-RUN)") (class "Default")
      (node (ref "C54") (pin "2") (pinfunction "2_2") (pintype "passive"))
      (node (ref "R37") (pin "2") (pinfunction "2_2") (pintype "passive"))
      (node (ref "U10") (pin "13") (pinfunction "RUN_13") (pintype "passive"))
      (node (ref "U10") (pin "14") (pinfunction "SVIN_14") (pintype "passive"))
    )
    (net (code "34") (name "Net-(U10-TMON)") (class "Default")
      (node (ref "TMON1") (pin "1") (pinfunction "1_1") (pintype "passive"))
      (node (ref "U10") (pin "5") (pinfunction "TMON_5") (pintype "passive"))
    )
    (net (code "35") (name "Net-(U10-TSET)") (class "Default")
      (node (ref "R62") (pin "1") (pinfunction "1_1") (pintype "passive"))
      (node (ref "R68") (pin "1") (pinfunction "1_1") (pintype "passive"))
      (node (ref "U10") (pin "4") (pinfunction "TSET_4") (pintype "passive"))
    )
    (net (code "36") (name "Net-(U10-VON)") (class "Default")
      (node (ref "C52") (pin "1") (pinfunction "1_1") (pintype "passive"))
      (node (ref "L15") (pin "1") (pinfunction "1_1") (pintype "passive"))
      (node (ref "U10") (pin "19") (pinfunction "SW_19") (pintype "passive"))
      (node (ref "U10") (pin "20") (pinfunction "SW_20") (pintype "passive"))
      (node (ref "U10") (pin "3") (pinfunction "VON_3") (pintype "passive"))
    )
    (net (code "37") (name "Net-(U11-BOOST)") (class "Default")
      (node (ref "C53") (pin "2") (pinfunction "2_2") (pintype "passive"))
      (node (ref "U11") (pin "1") (pinfunction "BOOST_1") (pintype "passive"))
    )
    (net (code "38") (name "Net-(U11-FB)") (class "Default")
      (node (ref "C68") (pin "1") (pinfunction "1_1") (pintype "passive"))
      (node (ref "R61") (pin "1") (pinfunction "1_1") (pintype "passive"))
      (node (ref "R65") (pin "2") (pinfunction "2_2") (pintype "passive"))
      (node (ref "U11") (pin "10") (pinfunction "FB_10") (pintype "passive"))
    )
    (net (code "39") (name "Net-(U11-IMONin)") (class "Default")
      (node (ref "R74") (pin "2") (pinfunction "2_2") (pintype "passive"))
      (node (ref "U11") (pin "7") (pinfunction "IMONin_7") (pintype "passive"))
    )
    (net (code "40") (name "Net-(U11-IMONout)") (class "Default")
      (node (ref "R73") (pin "2") (pinfunction "2_2") (pintype "passive"))
      (node (ref "U11") (pin "8") (pinfunction "IMONout_8") (pintype "passive"))
    )
    (net (code "41") (name "Net-(U11-INTVCC)") (class "Default")
      (node (ref "C59") (pin "2") (pinfunction "2_2") (pintype "passive"))
      (node (ref "R63") (pin "2") (pinfunction "2_2") (pintype "passive"))
      (node (ref "U11") (pin "11") (pinfunction "ITH_11") (pintype "passive"))
      (node (ref "U11") (pin "2") (pinfunction "INTVCC_2") (pintype "passive"))
      (node (ref "U11") (pin "9") (pinfunction "TRACK/SS_9") (pintype "passive"))
      (node (ref "U18") (pin "5") (pinfunction "Vcc_5") (pintype "power_in"))
    )
    (net (code "42") (name "Net-(U11-MODE{slash}SYNC)") (class "Default")
      (node (ref "U11") (pin "17") (pinfunction "MODE/SYNC_17") (pintype "passive"))
      (node (ref "U18") (pin "1") (pinfunction "Out_1") (pintype "passive"))
    )
    (net (code "43") (name "Net-(U11-PGND{slash}EXPPAD)") (class "Default")
      (node (ref "C56") (pin "2") (pinfunction "2_2") (pintype "passive"))
      (node (ref "R109") (pin "2") (pinfunction "2_2") (pintype "passive"))
      (node (ref "R65") (pin "1") (pinfunction "1_1") (pintype "passive"))
      (node (ref "R67") (pin "1") (pinfunction "1_1") (pintype "passive"))
      (node (ref "R69") (pin "2") (pinfunction "2_2") (pintype "passive"))
      (node (ref "R73") (pin "1") (pinfunction "1_1") (pintype "passive"))
      (node (ref "R74") (pin "1") (pinfunction "1_1") (pintype "passive"))
      (node (ref "U11") (pin "21") (pinfunction "PGND/EXPPAD_21") (pintype "passive"))
      (node (ref "U11") (pin "6") (pinfunction "SGND_6") (pintype "passive"))
      (node (ref "U18") (pin "2") (pinfunction "A_2") (pintype "passive"))
    )
    (net (code "44") (name "Net-(U11-RT)") (class "Default")
      (node (ref "R67") (pin "2") (pinfunction "2_2") (pintype "passive"))
      (node (ref "U11") (pin "12") (pinfunction "RT_12") (pintype "passive"))
    )
    (net (code "45") (name "Net-(U11-RUN)") (class "Default")
      (node (ref "C50") (pin "2") (pinfunction "2_2") (pintype "passive"))
      (node (ref "R36") (pin "1") (pinfunction "1_1") (pintype "passive"))
      (node (ref "U11") (pin "13") (pinfunction "RUN_13") (pintype "passive"))
      (node (ref "U11") (pin "14") (pinfunction "SVIN_14") (pintype "passive"))
    )
    (net (code "46") (name "Net-(U11-TMON)") (class "Default")
      (node (ref "TMON2") (pin "1") (pinfunction "1_1") (pintype "passive"))
      (node (ref "U11") (pin "5") (pinfunction "TMON_5") (pintype "passive"))
    )
    (net (code "47") (name "Net-(U11-TSET)") (class "Default")
      (node (ref "R63") (pin "1") (pinfunction "1_1") (pintype "passive"))
      (node (ref "R69") (pin "1") (pinfunction "1_1") (pintype "passive"))
      (node (ref "U11") (pin "4") (pinfunction "TSET_4") (pintype "passive"))
    )
    (net (code "48") (name "Net-(U11-VON)") (class "Default")
      (node (ref "C53") (pin "1") (pinfunction "1_1") (pintype "passive"))
      (node (ref "L16") (pin "1") (pinfunction "1_1") (pintype "passive"))
      (node (ref "U11") (pin "19") (pinfunction "SW_19") (pintype "passive"))
      (node (ref "U11") (pin "20") (pinfunction "SW_20") (pintype "passive"))
      (node (ref "U11") (pin "3") (pinfunction "VON_3") (pintype "passive"))
    )
    (net (code "49") (name "Net-(U12-ADJ)") (class "Default")
      (node (ref "R27") (pin "2") (pinfunction "2_2") (pintype "passive"))
      (node (ref "R28") (pin "1") (pinfunction "1_1") (pintype "passive"))
      (node (ref "U12") (pin "2") (pinfunction "ADJ_2") (pintype "passive"))
    )
    (net (code "50") (name "Net-(U12-BYP)") (class "Default")
      (node (ref "C109") (pin "1") (pinfunction "1_1") (pintype "passive"))
      (node (ref "U12") (pin "3") (pinfunction "BYP_3") (pintype "passive"))
    )
    (net (code "51") (name "Net-(U12-IN)") (class "Default")
      (node (ref "C98") (pin "1") (pinfunction "1_1") (pintype "passive"))
      (node (ref "L10") (pin "2") (pinfunction "2_2") (pintype "passive"))
      (node (ref "U12") (pin "8") (pinfunction "IN_8") (pintype "power_in"))
    )
    (net (code "52") (name "Net-(U12-SHDN)") (class "Default")
      (node (ref "C95") (pin "1") (pinfunction "1_1") (pintype "passive"))
      (node (ref "R35") (pin "2") (pinfunction "2_2") (pintype "passive"))
      (node (ref "U12") (pin "5") (pinfunction "SHDN_5") (pintype "passive"))
      (node (ref "U13") (pin "6") (pinfunction "SHDN_6") (pintype "passive"))
      (node (ref "U14") (pin "5") (pinfunction "SHDN_5") (pintype "passive"))
    )
    (net (code "53") (name "Net-(U13-ILim2)") (class "Default")
      (node (ref "C101") (pin "2") (pinfunction "2_2") (pintype "passive"))
      (node (ref "L11") (pin "1") (pinfunction "1_1") (pintype "passive"))
      (node (ref "R38") (pin "2") (pinfunction "2_2") (pintype "passive"))
      (node (ref "U13") (pin "1") (pinfunction "IN_1") (pintype "power_in"))
      (node (ref "U13") (pin "2") (pinfunction "ILim2_2") (pintype "passive"))
      (node (ref "U13") (pin "8") (pinfunction "IN_8") (pintype "power_in"))
    )
    (net (code "54") (name "Net-(U13-ILim4)") (class "Default")
      (node (ref "R38") (pin "1") (pinfunction "1_1") (pintype "passive"))
      (node (ref "U13") (pin "7") (pinfunction "ILim4_7") (pintype "passive"))
    )
    (net (code "55") (name "Net-(U13-SENSE)") (class "Default")
      (node (ref "R39") (pin "2") (pinfunction "2_2") (pintype "passive"))
      (node (ref "R40") (pin "1") (pinfunction "1_1") (pintype "passive"))
      (node (ref "U13") (pin "4") (pinfunction "SENSE_4") (pintype "power_in"))
    )
    (net (code "56") (name "Net-(U14-ADJ)") (class "Default")
      (node (ref "R41") (pin "2") (pinfunction "2_2") (pintype "passive"))
      (node (ref "R42") (pin "1") (pinfunction "1_1") (pintype "passive"))
      (node (ref "U14") (pin "2") (pinfunction "ADJ_2") (pintype "passive"))
    )
    (net (code "57") (name "Net-(U14-BYP)") (class "Default")
      (node (ref "C103") (pin "1") (pinfunction "1_1") (pintype "passive"))
      (node (ref "U14") (pin "3") (pinfunction "BYP_3") (pintype "passive"))
    )
    (net (code "58") (name "Net-(U14-IN)") (class "Default")
      (node (ref "C111") (pin "1") (pinfunction "1_1") (pintype "passive"))
      (node (ref "L12") (pin "2") (pinfunction "2_2") (pintype "passive"))
      (node (ref "U14") (pin "8") (pinfunction "IN_8") (pintype "power_in"))
    )
    (net (code "59") (name "Net-(U18-+)") (class "Default")
      (node (ref "R71") (pin "1") (pinfunction "1_1") (pintype "passive"))
      (node (ref "R75") (pin "1") (pinfunction "1_1") (pintype "passive"))
      (node (ref "U18") (pin "3") (pinfunction "+_3") (pintype "passive"))
    )
    (net (code "60") (name "Net-(U19-ADJ)") (class "Default")
      (node (ref "R85") (pin "2") (pinfunction "2_2") (pintype "passive"))
      (node (ref "R86") (pin "1") (pinfunction "1_1") (pintype "passive"))
      (node (ref "U19") (pin "2") (pinfunction "ADJ_2") (pintype "passive"))
    )
    (net (code "61") (name "Net-(U19-BYP)") (class "Default")
      (node (ref "C82") (pin "1") (pinfunction "1_1") (pintype "passive"))
      (node (ref "U19") (pin "3") (pinfunction "BYP_3") (pintype "passive"))
    )
    (net (code "62") (name "Net-(U19-IN)") (class "Default")
      (node (ref "C96") (pin "1") (pinfunction "1_1") (pintype "passive"))
      (node (ref "L17") (pin "2") (pinfunction "2_2") (pintype "passive"))
      (node (ref "U19") (pin "8") (pinfunction "IN_8") (pintype "power_in"))
    )
    (net (code "63") (name "Net-(U19-SHDN)") (class "Default")
      (node (ref "C93") (pin "2") (pinfunction "2_2") (pintype "passive"))
      (node (ref "R33") (pin "2") (pinfunction "2_2") (pintype "passive"))
      (node (ref "R34") (pin "1") (pinfunction "1_1") (pintype "passive"))
      (node (ref "U19") (pin "5") (pinfunction "SHDN_5") (pintype "passive"))
    )
    (net (code "64") (name "unconnected-(J4-Pad2)") (class "Default")
      (node (ref "J4") (pin "2") (pinfunction "2_2") (pintype "passive"))
    )
    (net (code "65") (name "unconnected-(U10-PGOOD-Pad18)") (class "Default")
      (node (ref "U10") (pin "18") (pinfunction "PGOOD_18") (pintype "passive+no_connect"))
    )
    (net (code "66") (name "unconnected-(U11-PGOOD-Pad18)") (class "Default")
      (node (ref "U11") (pin "18") (pinfunction "PGOOD_18") (pintype "passive+no_connect"))
    )
    (net (code "67") (name "unconnected-(U12-NC-Pad6)") (class "Default")
      (node (ref "U12") (pin "6") (pinfunction "NC_6") (pintype "passive"))
    )
    (net (code "68") (name "unconnected-(U12-NC-Pad7)") (class "Default")
      (node (ref "U12") (pin "7") (pinfunction "NC_7") (pintype "passive"))
    )
    (net (code "69") (name "unconnected-(U14-NC-Pad6)") (class "Default")
      (node (ref "U14") (pin "6") (pinfunction "NC_6") (pintype "passive"))
    )
    (net (code "70") (name "unconnected-(U14-NC-Pad7)") (class "Default")
      (node (ref "U14") (pin "7") (pinfunction "NC_7") (pintype "passive"))
    )
    (net (code "71") (name "unconnected-(U19-NC-Pad6)") (class "Default")
      (node (ref "U19") (pin "6") (pinfunction "NC_6") (pintype "passive"))
    )
    (net (code "72") (name "unconnected-(U19-NC-Pad7)") (class "Default")
      (node (ref "U19") (pin "7") (pinfunction "NC_7") (pintype "passive"))
    )
  )
)
